# hoperf-rfm9x-lora-breakout.net
KiCad netlist of a schematic drawn in EAGLE
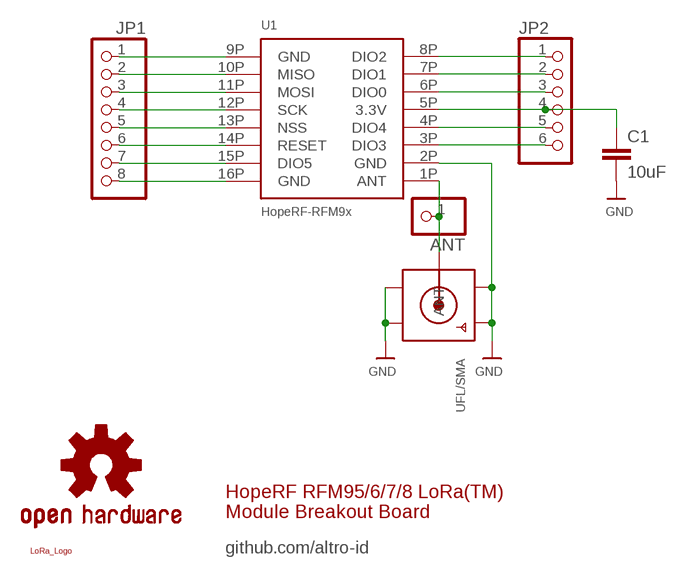
[diagram p0: schematic, sheet 1]

(export (version "E")
  (design (tool "Eeschema 10.0.6"))
  (components
    (comp (ref "ANT")
      (value "HEADER-1X1ROUND")
      (footprint "eagle-import:1X01_ROUND")
      (libsource (lib "eagle-import") (part "HEADER-1X1ROUND"))
    )
    (comp (ref "C1")
      (value "10uF")
      (footprint "eagle-import:0805_MP")
      (libsource (lib "eagle-import") (part "CAP0805"))
    )
    (comp (ref "JP1")
      (value "HEADER-1X876MIL")
      (footprint "eagle-import:1X08_ROUND_76")
      (libsource (lib "eagle-import") (part "HEADER-1X876MIL"))
    )
    (comp (ref "JP2")
      (value "HEADER-1X676MIL")
      (footprint "eagle-import:1X06_ROUND_76")
      (libsource (lib "eagle-import") (part "HEADER-1X676MIL"))
    )
    (comp (ref "LOGO1")
      (value "OSHW-LOGOS")
      (footprint "eagle-import:OSHW-LOGO-S")
      (libsource (lib "eagle-import") (part "OSHW-LOGOS"))
    )
    (comp (ref "U$3")
      (value "LORA_LOGO")
      (footprint "eagle-import:LORA_LOGO")
      (libsource (lib "eagle-import") (part "LORA_LOGO"))
    )
    (comp (ref "U1")
      (value "HopeRF-RFM9x")
      (footprint "eagle-import:RFM9X_SMT")
      (libsource (lib "eagle-import") (part "RFM9X_LORA"))
    )
    (comp (ref "UFL/SMA")
      (value "MICROBUILDER_SMACONNECTOR_EDGE_UFL")
      (footprint "eagle-import:MICROBUILDER_SMA_EDGELAUNCH_UFL")
      (libsource (lib "eagle-import") (part "MICROBUILDER_SMACONNECTOR_EDGE_UFL"))
    )
  )
  (nets
    (net (code "1") (name "GND") (class "Default")
      (node (ref "C1") (pin "2") (pinfunction "2_2") (pintype "passive"))
      (node (ref "JP1") (pin "1") (pinfunction "1_1") (pintype "passive"))
      (node (ref "JP1") (pin "8") (pinfunction "8_8") (pintype "passive"))
      (node (ref "U1") (pin "16P") (pinfunction "GND_16P") (pintype "bidirectional"))
      (node (ref "U1") (pin "2P") (pinfunction "GND_2P") (pintype "bidirectional"))
      (node (ref "U1") (pin "9P") (pinfunction "GND_9P") (pintype "bidirectional"))
      (node (ref "UFL/SMA") (pin "GND@1") (pinfunction "GND1_GND@1") (pintype "power_in"))
      (node (ref "UFL/SMA") (pin "GND@2") (pinfunction "GND2_GND@2") (pintype "power_in"))
      (node (ref "UFL/SMA") (pin "GND@3") (pinfunction "GND3_GND@3") (pintype "power_in"))
      (node (ref "UFL/SMA") (pin "GND@4") (pinfunction "GND4_GND@4") (pintype "power_in"))
    )
    (net (code "2") (name "Net-(U1-3.3V)") (class "Default")
      (node (ref "C1") (pin "1") (pinfunction "1_1") (pintype "passive"))
      (node (ref "JP2") (pin "4") (pinfunction "4_4") (pintype "passive"))
      (node (ref "U1") (pin "5P") (pinfunction "3.3V_5P") (pintype "bidirectional"))
    )
    (net (code "3") (name "Net-(U1-ANT)") (class "Default")
      (node (ref "ANT") (pin "1") (pinfunction "1_1") (pintype "passive"))
      (node (ref "U1") (pin "1P") (pinfunction "ANT_1P") (pintype "bidirectional"))
      (node (ref "UFL/SMA") (pin "P") (pinfunction "ANT_P") (pintype "bidirectional"))
    )
    (net (code "4") (name "Net-(U1-DIO0)") (class "Default")
      (node (ref "JP2") (pin "3") (pinfunction "3_3") (pintype "passive"))
      (node (ref "U1") (pin "6P") (pinfunction "DIO0_6P") (pintype "bidirectional"))
    )
    (net (code "5") (name "Net-(U1-DIO1)") (class "Default")
      (node (ref "JP2") (pin "2") (pinfunction "2_2") (pintype "passive"))
      (node (ref "U1") (pin "7P") (pinfunction "DIO1_7P") (pintype "bidirectional"))
    )
    (net (code "6") (name "Net-(U1-DIO2)") (class "Default")
      (node (ref "JP2") (pin "1") (pinfunction "1_1") (pintype "passive"))
      (node (ref "U1") (pin "8P") (pinfunction "DIO2_8P") (pintype "bidirectional"))
    )
    (net (code "7") (name "Net-(U1-DIO3)") (class "Default")
      (node (ref "JP2") (pin "6") (pinfunction "6_6") (pintype "passive"))
      (node (ref "U1") (pin "3P") (pinfunction "DIO3_3P") (pintype "bidirectional"))
    )
    (net (code "8") (name "Net-(U1-DIO4)") (class "Default")
      (node (ref "JP2") (pin "5") (pinfunction "5_5") (pintype "passive"))
      (node (ref "U1") (pin "4P") (pinfunction "DIO4_4P") (pintype "bidirectional"))
    )
    (net (code "9") (name "Net-(U1-DIO5)") (class "Default")
      (node (ref "JP1") (pin "7") (pinfunction "7_7") (pintype "passive"))
      (node (ref "U1") (pin "15P") (pinfunction "DIO5_15P") (pintype "bidirectional"))
    )
    (net (code "10") (name "Net-(U1-MISO)") (class "Default")
      (node (ref "JP1") (pin "2") (pinfunction "2_2") (pintype "passive"))
      (node (ref "U1") (pin "10P") (pinfunction "MISO_10P") (pintype "bidirectional"))
    )
    (net (code "11") (name "Net-(U1-MOSI)") (class "Default")
      (node (ref "JP1") (pin "3") (pinfunction "3_3") (pintype "passive"))
      (node (ref "U1") (pin "11P") (pinfunction "MOSI_11P") (pintype "bidirectional"))
    )
    (net (code "12") (name "Net-(U1-NSS)") (class "Default")
      (node (ref "JP1") (pin "5") (pinfunction "5_5") (pintype "passive"))
      (node (ref "U1") (pin "13P") (pinfunction "NSS_13P") (pintype "bidirectional"))
    )
    (net (code "13") (name "Net-(U1-RESET)") (class "Default")
      (node (ref "JP1") (pin "6") (pinfunction "6_6") (pintype "passive"))
      (node (ref "U1") (pin "14P") (pinfunction "RESET_14P") (pintype "bidirectional"))
    )
    (net (code "14") (name "Net-(U1-SCK)") (class "Default")
      (node (ref "JP1") (pin "4") (pinfunction "4_4") (pintype "passive"))
      (node (ref "U1") (pin "12P") (pinfunction "SCK_12P") (pintype "bidirectional"))
    )
  )
)
